# SUSTAINA-Power-Distribution-Board.net
KiCad netlist of a schematic drawn in EAGLE
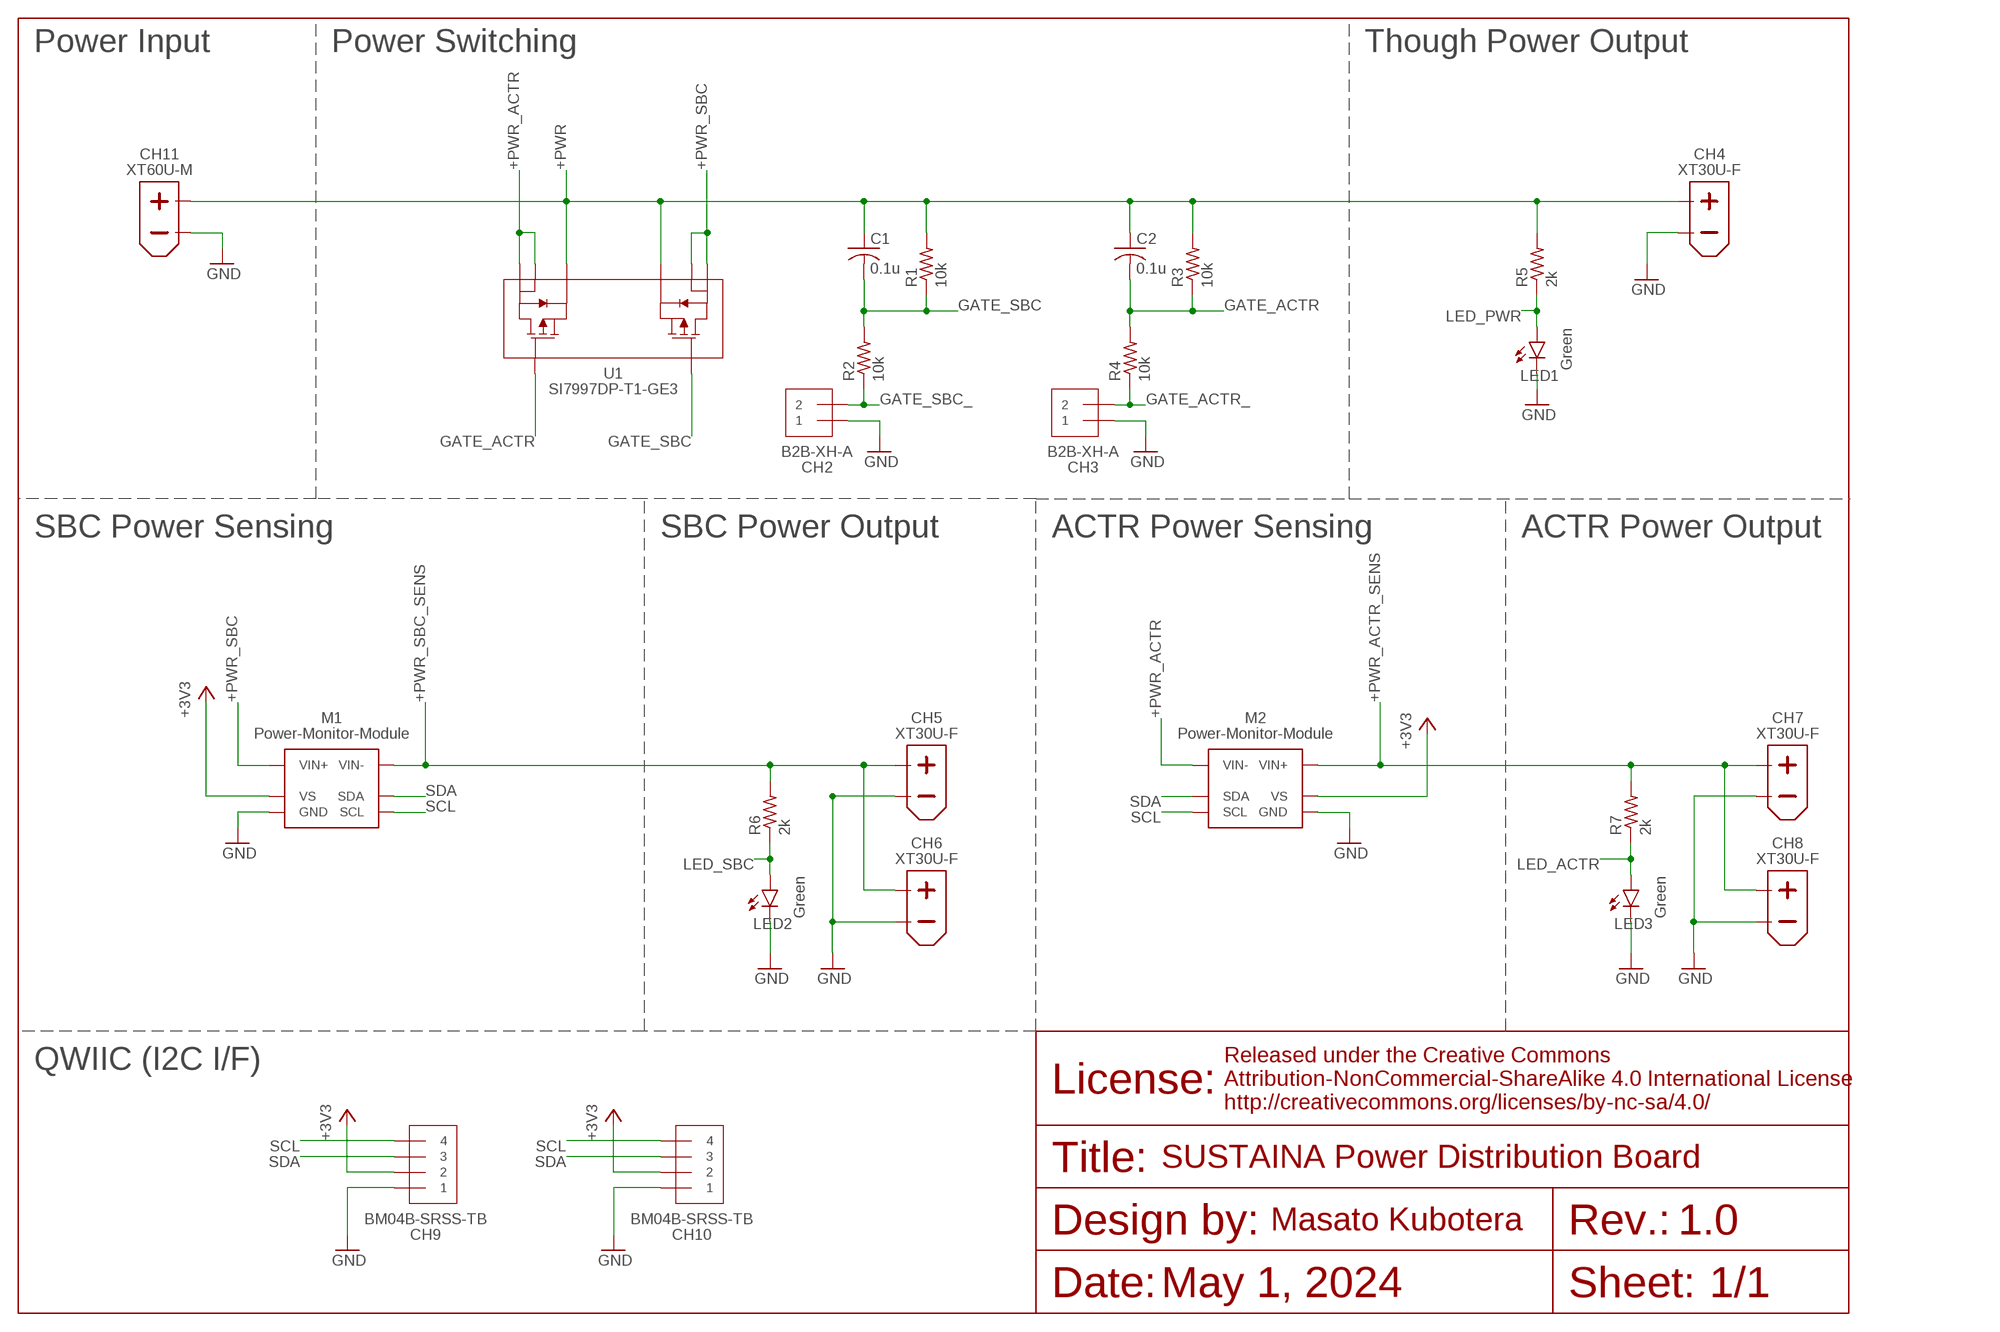
[diagram p0: schematic, sheet 1]

(export (version "E")
  (design (tool "Eeschema 10.0.6"))
  (components
    (comp (ref "C1")
      (value "0.1u")
      (footprint "eagle-import:C0603")
      (libsource (lib "eagle-import") (part "C-USC0603"))
    )
    (comp (ref "C2")
      (value "0.1u")
      (footprint "eagle-import:C0603")
      (libsource (lib "eagle-import") (part "C-USC0603"))
    )
    (comp (ref "CH2")
      (value "B2B-XH-A")
      (footprint "eagle-import:B2B-XH-A")
      (libsource (lib "eagle-import") (part "B2B-XH-A"))
    )
    (comp (ref "CH3")
      (value "B2B-XH-A")
      (footprint "eagle-import:B2B-XH-A")
      (libsource (lib "eagle-import") (part "B2B-XH-A"))
    )
    (comp (ref "CH4")
      (value "XT30U-F")
      (footprint "eagle-import:XT30U-F")
      (libsource (lib "eagle-import") (part "XT30U-F"))
    )
    (comp (ref "CH5")
      (value "XT30U-F")
      (footprint "eagle-import:XT30U-F")
      (libsource (lib "eagle-import") (part "XT30U-F"))
    )
    (comp (ref "CH6")
      (value "XT30U-F")
      (footprint "eagle-import:XT30U-F")
      (libsource (lib "eagle-import") (part "XT30U-F"))
    )
    (comp (ref "CH7")
      (value "XT30U-F")
      (footprint "eagle-import:XT30U-F")
      (libsource (lib "eagle-import") (part "XT30U-F"))
    )
    (comp (ref "CH8")
      (value "XT30U-F")
      (footprint "eagle-import:XT30U-F")
      (libsource (lib "eagle-import") (part "XT30U-F"))
    )
    (comp (ref "CH9")
      (value "BM04B-SRSS-TB")
      (footprint "eagle-import:BM04B-SRSS-TB")
      (libsource (lib "eagle-import") (part "BM04B-SRSS-TB"))
    )
    (comp (ref "CH10")
      (value "BM04B-SRSS-TB")
      (footprint "eagle-import:BM04B-SRSS-TB")
      (libsource (lib "eagle-import") (part "BM04B-SRSS-TB"))
    )
    (comp (ref "CH11")
      (value "XT60U-M")
      (footprint "eagle-import:XT60U-M")
      (libsource (lib "eagle-import") (part "XT60U-M"))
    )
    (comp (ref "LED1")
      (value "Green")
      (footprint "eagle-import:SML0603")
      (libsource (lib "eagle-import") (part "LEDSML0603"))
    )
    (comp (ref "LED2")
      (value "Green")
      (footprint "eagle-import:SML0603")
      (libsource (lib "eagle-import") (part "LEDSML0603"))
    )
    (comp (ref "LED3")
      (value "Green")
      (footprint "eagle-import:SML0603")
      (libsource (lib "eagle-import") (part "LEDSML0603"))
    )
    (comp (ref "M1")
      (value "POWER-MONITOR-MODULE")
      (footprint "eagle-import:POWER-MONITOR-MODULE")
      (libsource (lib "eagle-import") (part "POWER-MONITOR-MODULE"))
    )
    (comp (ref "M2")
      (value "POWER-MONITOR-MODULE")
      (footprint "eagle-import:POWER-MONITOR-MODULE")
      (libsource (lib "eagle-import") (part "POWER-MONITOR-MODULE"))
    )
    (comp (ref "R1")
      (value "10k")
      (footprint "eagle-import:R0603")
      (libsource (lib "eagle-import") (part "R-US_R0603"))
    )
    (comp (ref "R2")
      (value "10k")
      (footprint "eagle-import:R0603")
      (libsource (lib "eagle-import") (part "R-US_R0603"))
    )
    (comp (ref "R3")
      (value "10k")
      (footprint "eagle-import:R0603")
      (libsource (lib "eagle-import") (part "R-US_R0603"))
    )
    (comp (ref "R4")
      (value "10k")
      (footprint "eagle-import:R0603")
      (libsource (lib "eagle-import") (part "R-US_R0603"))
    )
    (comp (ref "R5")
      (value "2k")
      (footprint "eagle-import:R0603")
      (libsource (lib "eagle-import") (part "R-US_R0603"))
    )
    (comp (ref "R6")
      (value "2k")
      (footprint "eagle-import:R0603")
      (libsource (lib "eagle-import") (part "R-US_R0603"))
    )
    (comp (ref "R7")
      (value "2k")
      (footprint "eagle-import:R0603")
      (libsource (lib "eagle-import") (part "R-US_R0603"))
    )
    (comp (ref "U1")
      (value "SI7997DP-T1-GE3")
      (footprint "eagle-import:POWERPAK_SO-8_VIS")
      (fields (field (name "COPYRIGHT") "Copyright (C) 2024 Ultra Librarian. All rights reserved."))
      (libsource (lib "eagle-import") (part "SI7997DP-T1-GE3"))
    )
  )
  (nets
    (net (code "1") (name "+3V3") (class "Default")
      (node (ref "CH10") (pin "2") (pinfunction "2_2") (pintype "bidirectional"))
      (node (ref "CH9") (pin "2") (pinfunction "2_2") (pintype "bidirectional"))
      (node (ref "M1") (pin "VS") (pinfunction "VS_VS") (pintype "power_in"))
      (node (ref "M2") (pin "VS") (pinfunction "VS_VS") (pintype "power_in"))
    )
    (net (code "2") (name "/+PWR") (class "Default")
      (node (ref "C1") (pin "1") (pinfunction "1_1") (pintype "passive"))
      (node (ref "C2") (pin "1") (pinfunction "1_1") (pintype "passive"))
      (node (ref "CH11") (pin "+") (pinfunction "+_+") (pintype "power_in"))
      (node (ref "CH4") (pin "+") (pinfunction "+_+") (pintype "power_in"))
      (node (ref "R1") (pin "2") (pinfunction "2_2") (pintype "passive"))
      (node (ref "R3") (pin "2") (pinfunction "2_2") (pintype "passive"))
      (node (ref "R5") (pin "2") (pinfunction "2_2") (pintype "passive"))
      (node (ref "U1") (pin "1") (pinfunction "S1_1") (pintype "passive"))
      (node (ref "U1") (pin "3") (pinfunction "S2_3") (pintype "passive"))
    )
    (net (code "3") (name "/+PWR_ACTR") (class "Default")
      (node (ref "M2") (pin "VIN-1") (pinfunction "VIN-_VIN-1") (pintype "power_in"))
      (node (ref "M2") (pin "VIN-10") (pinfunction "VIN-_VIN-10") (pintype "power_in"))
      (node (ref "M2") (pin "VIN-2") (pinfunction "VIN-_VIN-2") (pintype "power_in"))
      (node (ref "M2") (pin "VIN-3") (pinfunction "VIN-_VIN-3") (pintype "power_in"))
      (node (ref "M2") (pin "VIN-4") (pinfunction "VIN-_VIN-4") (pintype "power_in"))
      (node (ref "M2") (pin "VIN-5") (pinfunction "VIN-_VIN-5") (pintype "power_in"))
      (node (ref "M2") (pin "VIN-6") (pinfunction "VIN-_VIN-6") (pintype "power_in"))
      (node (ref "M2") (pin "VIN-7") (pinfunction "VIN-_VIN-7") (pintype "power_in"))
      (node (ref "M2") (pin "VIN-8") (pinfunction "VIN-_VIN-8") (pintype "power_in"))
      (node (ref "M2") (pin "VIN-9") (pinfunction "VIN-_VIN-9") (pintype "power_in"))
      (node (ref "U1") (pin "7") (pinfunction "D1_7") (pintype "passive"))
      (node (ref "U1") (pin "8") (pinfunction "D1_2_8") (pintype "passive"))
    )
    (net (code "4") (name "/+PWR_ACTR_SENS") (class "Default")
      (node (ref "CH7") (pin "+") (pinfunction "+_+") (pintype "power_in"))
      (node (ref "CH8") (pin "+") (pinfunction "+_+") (pintype "power_in"))
      (node (ref "M2") (pin "VIN+1") (pinfunction "VIN+_VIN+1") (pintype "power_in"))
      (node (ref "M2") (pin "VIN+10") (pinfunction "VIN+_VIN+10") (pintype "power_in"))
      (node (ref "M2") (pin "VIN+2") (pinfunction "VIN+_VIN+2") (pintype "power_in"))
      (node (ref "M2") (pin "VIN+3") (pinfunction "VIN+_VIN+3") (pintype "power_in"))
      (node (ref "M2") (pin "VIN+4") (pinfunction "VIN+_VIN+4") (pintype "power_in"))
      (node (ref "M2") (pin "VIN+5") (pinfunction "VIN+_VIN+5") (pintype "power_in"))
      (node (ref "M2") (pin "VIN+6") (pinfunction "VIN+_VIN+6") (pintype "power_in"))
      (node (ref "M2") (pin "VIN+7") (pinfunction "VIN+_VIN+7") (pintype "power_in"))
      (node (ref "M2") (pin "VIN+8") (pinfunction "VIN+_VIN+8") (pintype "power_in"))
      (node (ref "M2") (pin "VIN+9") (pinfunction "VIN+_VIN+9") (pintype "power_in"))
      (node (ref "R7") (pin "2") (pinfunction "2_2") (pintype "passive"))
    )
    (net (code "5") (name "/+PWR_SBC") (class "Default")
      (node (ref "M1") (pin "VIN+1") (pinfunction "VIN+_VIN+1") (pintype "power_in"))
      (node (ref "M1") (pin "VIN+10") (pinfunction "VIN+_VIN+10") (pintype "power_in"))
      (node (ref "M1") (pin "VIN+2") (pinfunction "VIN+_VIN+2") (pintype "power_in"))
      (node (ref "M1") (pin "VIN+3") (pinfunction "VIN+_VIN+3") (pintype "power_in"))
      (node (ref "M1") (pin "VIN+4") (pinfunction "VIN+_VIN+4") (pintype "power_in"))
      (node (ref "M1") (pin "VIN+5") (pinfunction "VIN+_VIN+5") (pintype "power_in"))
      (node (ref "M1") (pin "VIN+6") (pinfunction "VIN+_VIN+6") (pintype "power_in"))
      (node (ref "M1") (pin "VIN+7") (pinfunction "VIN+_VIN+7") (pintype "power_in"))
      (node (ref "M1") (pin "VIN+8") (pinfunction "VIN+_VIN+8") (pintype "power_in"))
      (node (ref "M1") (pin "VIN+9") (pinfunction "VIN+_VIN+9") (pintype "power_in"))
      (node (ref "U1") (pin "5") (pinfunction "D2_5") (pintype "passive"))
      (node (ref "U1") (pin "6") (pinfunction "D2_2_6") (pintype "passive"))
    )
    (net (code "6") (name "/+PWR_SBC_SENS") (class "Default")
      (node (ref "CH5") (pin "+") (pinfunction "+_+") (pintype "power_in"))
      (node (ref "CH6") (pin "+") (pinfunction "+_+") (pintype "power_in"))
      (node (ref "M1") (pin "VIN-1") (pinfunction "VIN-_VIN-1") (pintype "power_in"))
      (node (ref "M1") (pin "VIN-10") (pinfunction "VIN-_VIN-10") (pintype "power_in"))
      (node (ref "M1") (pin "VIN-2") (pinfunction "VIN-_VIN-2") (pintype "power_in"))
      (node (ref "M1") (pin "VIN-3") (pinfunction "VIN-_VIN-3") (pintype "power_in"))
      (node (ref "M1") (pin "VIN-4") (pinfunction "VIN-_VIN-4") (pintype "power_in"))
      (node (ref "M1") (pin "VIN-5") (pinfunction "VIN-_VIN-5") (pintype "power_in"))
      (node (ref "M1") (pin "VIN-6") (pinfunction "VIN-_VIN-6") (pintype "power_in"))
      (node (ref "M1") (pin "VIN-7") (pinfunction "VIN-_VIN-7") (pintype "power_in"))
      (node (ref "M1") (pin "VIN-8") (pinfunction "VIN-_VIN-8") (pintype "power_in"))
      (node (ref "M1") (pin "VIN-9") (pinfunction "VIN-_VIN-9") (pintype "power_in"))
      (node (ref "R6") (pin "2") (pinfunction "2_2") (pintype "passive"))
    )
    (net (code "7") (name "/GATE_ACTR") (class "Default")
      (node (ref "C2") (pin "2") (pinfunction "2_2") (pintype "passive"))
      (node (ref "R3") (pin "1") (pinfunction "1_1") (pintype "passive"))
      (node (ref "R4") (pin "2") (pinfunction "2_2") (pintype "passive"))
      (node (ref "U1") (pin "2") (pinfunction "G1_2") (pintype "passive"))
    )
    (net (code "8") (name "/GATE_ACTR_") (class "Default")
      (node (ref "CH3") (pin "2") (pinfunction "2_2") (pintype "bidirectional"))
      (node (ref "R4") (pin "1") (pinfunction "1_1") (pintype "passive"))
    )
    (net (code "9") (name "/GATE_SBC") (class "Default")
      (node (ref "C1") (pin "2") (pinfunction "2_2") (pintype "passive"))
      (node (ref "R1") (pin "1") (pinfunction "1_1") (pintype "passive"))
      (node (ref "R2") (pin "2") (pinfunction "2_2") (pintype "passive"))
      (node (ref "U1") (pin "4") (pinfunction "G2_4") (pintype "passive"))
    )
    (net (code "10") (name "/GATE_SBC_") (class "Default")
      (node (ref "CH2") (pin "2") (pinfunction "2_2") (pintype "bidirectional"))
      (node (ref "R2") (pin "1") (pinfunction "1_1") (pintype "passive"))
    )
    (net (code "11") (name "/LED_ACTR") (class "Default")
      (node (ref "LED3") (pin "A") (pinfunction "A_A") (pintype "passive"))
      (node (ref "R7") (pin "1") (pinfunction "1_1") (pintype "passive"))
    )
    (net (code "12") (name "/LED_PWR") (class "Default")
      (node (ref "LED1") (pin "A") (pinfunction "A_A") (pintype "passive"))
      (node (ref "R5") (pin "1") (pinfunction "1_1") (pintype "passive"))
    )
    (net (code "13") (name "/LED_SBC") (class "Default")
      (node (ref "LED2") (pin "A") (pinfunction "A_A") (pintype "passive"))
      (node (ref "R6") (pin "1") (pinfunction "1_1") (pintype "passive"))
    )
    (net (code "14") (name "/SCL") (class "Default")
      (node (ref "CH10") (pin "4") (pinfunction "4_4") (pintype "bidirectional"))
      (node (ref "CH9") (pin "4") (pinfunction "4_4") (pintype "bidirectional"))
      (node (ref "M1") (pin "SCL") (pinfunction "SCL_SCL") (pintype "bidirectional"))
      (node (ref "M2") (pin "SCL") (pinfunction "SCL_SCL") (pintype "bidirectional"))
    )
    (net (code "15") (name "/SDA") (class "Default")
      (node (ref "CH10") (pin "3") (pinfunction "3_3") (pintype "bidirectional"))
      (node (ref "CH9") (pin "3") (pinfunction "3_3") (pintype "bidirectional"))
      (node (ref "M1") (pin "SDA") (pinfunction "SDA_SDA") (pintype "bidirectional"))
      (node (ref "M2") (pin "SDA") (pinfunction "SDA_SDA") (pintype "bidirectional"))
    )
    (net (code "16") (name "GND") (class "Default")
      (node (ref "CH10") (pin "1") (pinfunction "1_1") (pintype "bidirectional"))
      (node (ref "CH11") (pin "-") (pinfunction "-_-") (pintype "power_in"))
      (node (ref "CH2") (pin "1") (pinfunction "1_1") (pintype "bidirectional"))
      (node (ref "CH3") (pin "1") (pinfunction "1_1") (pintype "bidirectional"))
      (node (ref "CH4") (pin "-") (pinfunction "-_-") (pintype "power_in"))
      (node (ref "CH5") (pin "-") (pinfunction "-_-") (pintype "power_in"))
      (node (ref "CH6") (pin "-") (pinfunction "-_-") (pintype "power_in"))
      (node (ref "CH7") (pin "-") (pinfunction "-_-") (pintype "power_in"))
      (node (ref "CH8") (pin "-") (pinfunction "-_-") (pintype "power_in"))
      (node (ref "CH9") (pin "1") (pinfunction "1_1") (pintype "bidirectional"))
      (node (ref "LED1") (pin "C") (pinfunction "C_C") (pintype "passive"))
      (node (ref "LED2") (pin "C") (pinfunction "C_C") (pintype "passive"))
      (node (ref "LED3") (pin "C") (pinfunction "C_C") (pintype "passive"))
      (node (ref "M1") (pin "GND") (pinfunction "GND_GND") (pintype "power_in"))
      (node (ref "M2") (pin "GND") (pinfunction "GND_GND") (pintype "power_in"))
    )
  )
)
